# RAM_EMMC_Power.net
KiCad netlist of a schematic drawn in Altium Designer
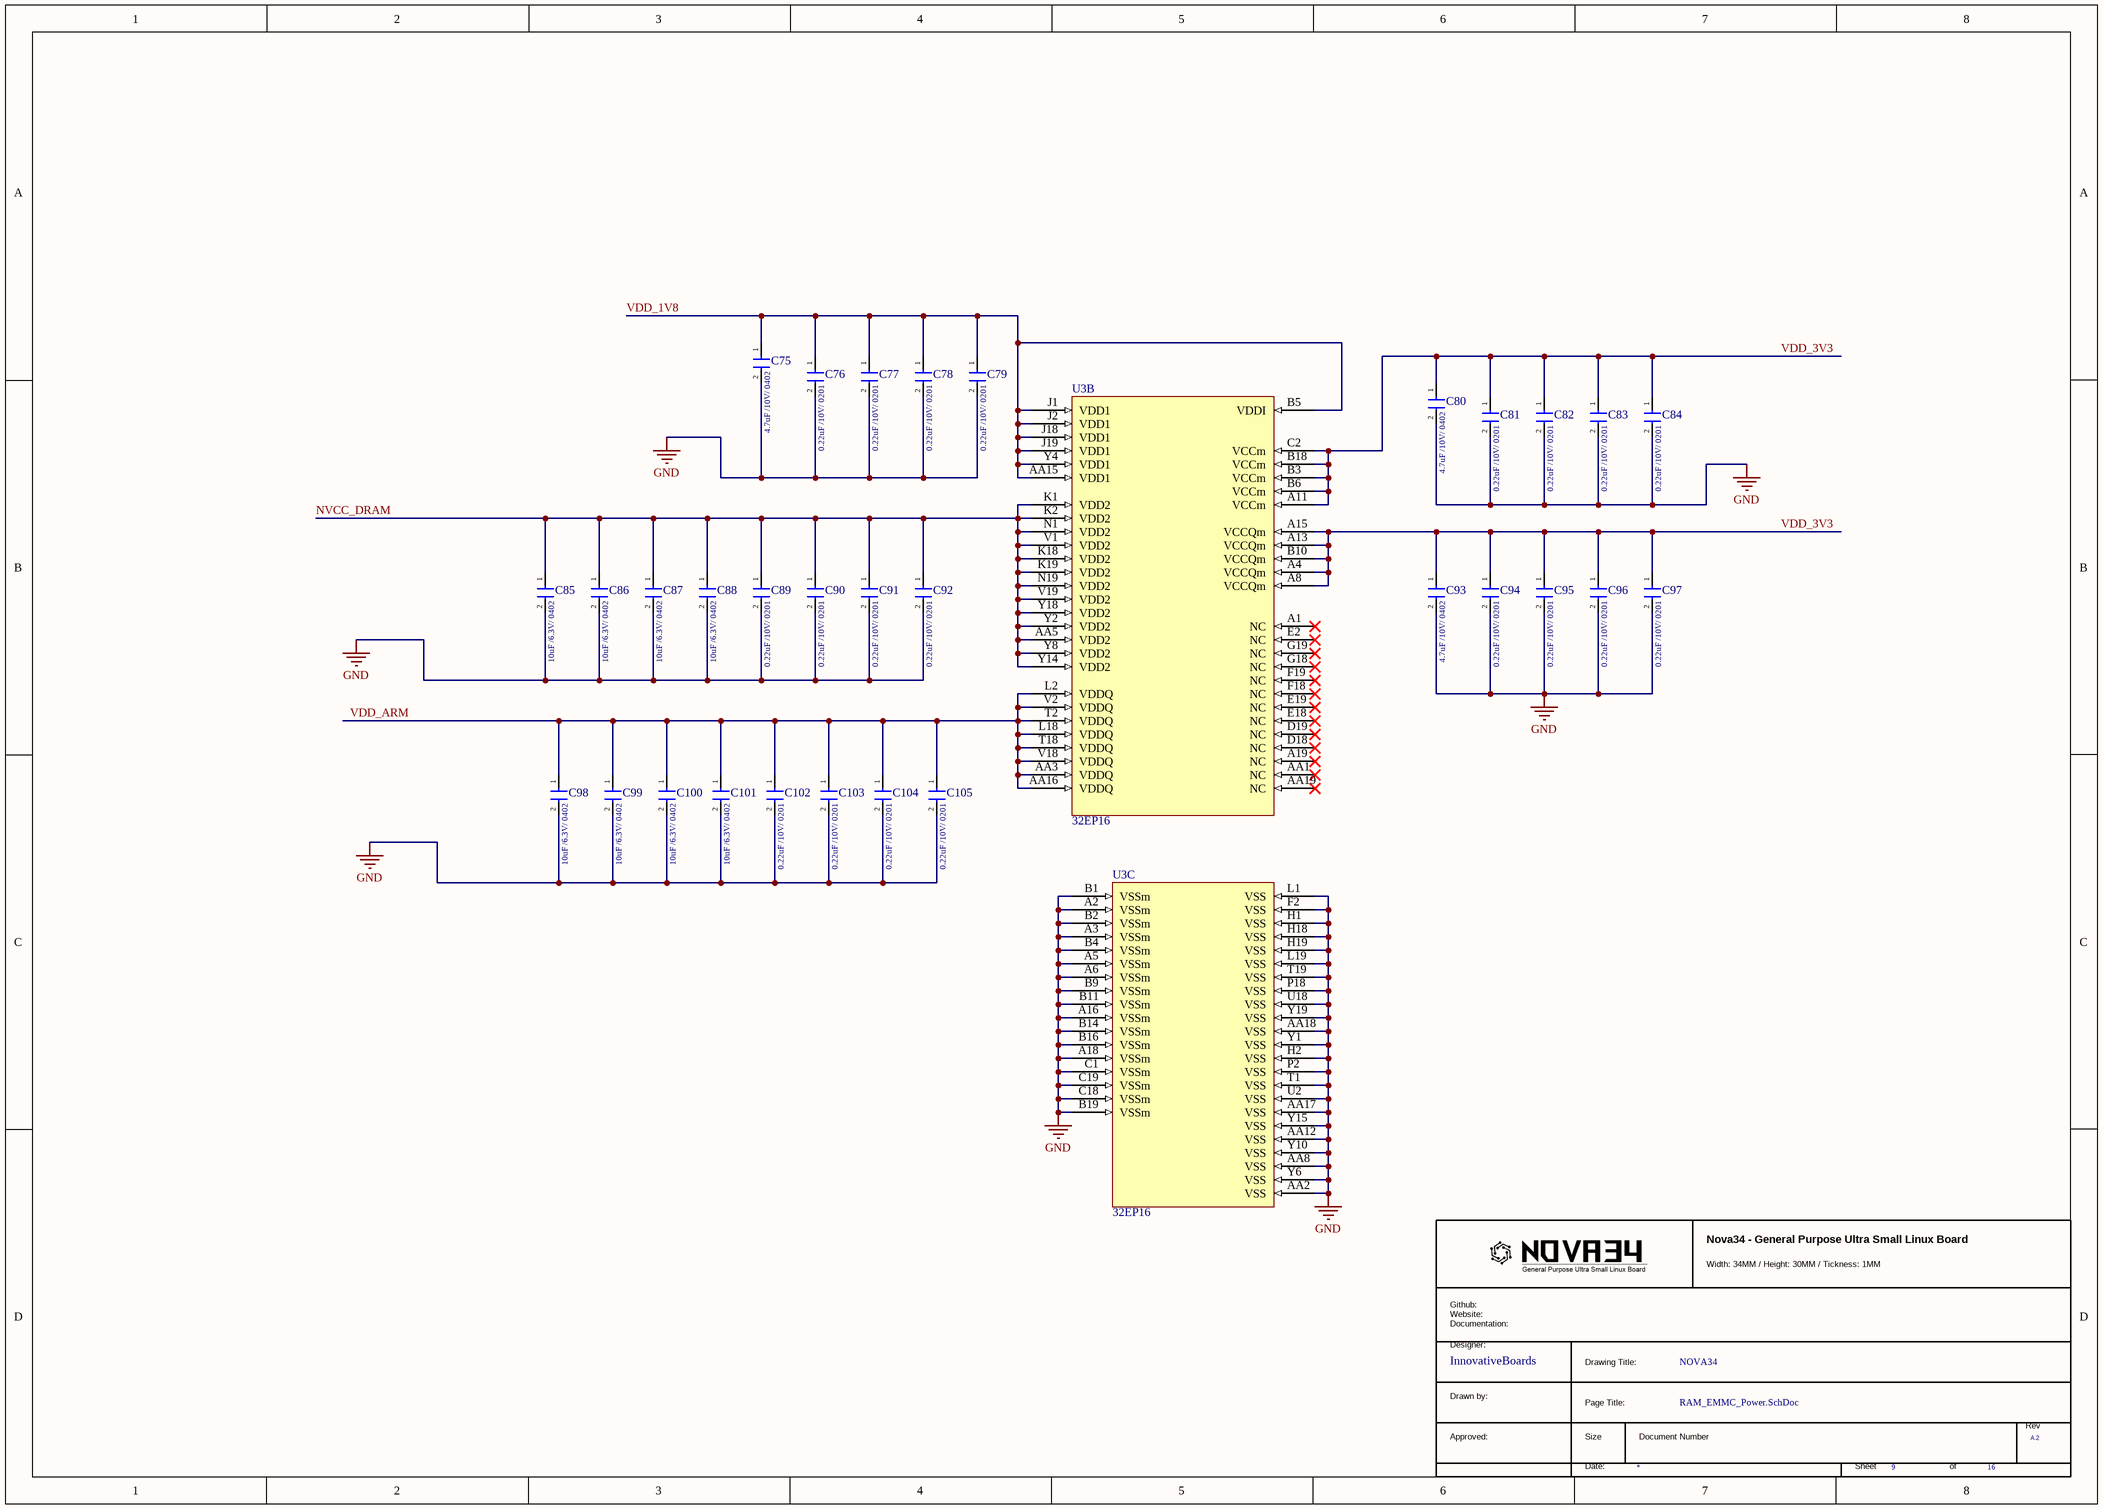
[diagram p0: RAM_EMMC_Power.SchDoc]

(export (version "E")
  (design (tool "Eeschema 10.0.6"))
  (components
    (comp (ref "*")
      (value "TitleBlock_MCPG")
      (fields (field (name "REVCODE") "A.2"))
      (libsource (lib "Nova_SCHLIB") (part "TitleBlock_MCPG"))
    )
    (comp (ref "C75")
      (value "4.7uF /10V/ 0402")
      (footprint "CAPC1005X70N")
      (description "Multilayer Ceramic Capacitors MLCC - SMD/SMT 0402 X6S 4.7 F 20 10VDC AEC-Q200")
      (fields
        (field (name "MANUFACTURER_PART_NUMBER") "GRT155C81A475ME13J")
        (field (name "MOUSER PART NUMBER") "81-GRT155C81A475ME3J")
      )
      (libsource (lib "Nova_SCHLIB") (part "GRT155C81A475ME13J"))
    )
    (comp (ref "C76")
      (value "0.22uF /10V/ 0201")
      (footprint "GRM033D70J224ME01D")
      (description "Multilayer Ceramic Capacitors MLCC - SMD/SMT 0201 10VDC 0.22 F 10 X6S")
      (fields
        (field (name "MANUFACTURER_PART_NUMBER") "GRM033C81A224KE01J")
        (field (name "MOUSER PART NUMBER") "81-GRM033C81A224KE1J")
      )
      (libsource (lib "Nova_SCHLIB") (part "GRM033C81A224KE01J"))
    )
    (comp (ref "C77")
      (value "0.22uF /10V/ 0201")
      (footprint "GRM033D70J224ME01D")
      (description "Multilayer Ceramic Capacitors MLCC - SMD/SMT 0201 10VDC 0.22 F 10 X6S")
      (fields
        (field (name "MANUFACTURER_PART_NUMBER") "GRM033C81A224KE01J")
        (field (name "MOUSER PART NUMBER") "81-GRM033C81A224KE1J")
      )
      (libsource (lib "Nova_SCHLIB") (part "GRM033C81A224KE01J"))
    )
    (comp (ref "C78")
      (value "0.22uF /10V/ 0201")
      (footprint "GRM033D70J224ME01D")
      (description "Multilayer Ceramic Capacitors MLCC - SMD/SMT 0201 10VDC 0.22 F 10 X6S")
      (fields
        (field (name "MANUFACTURER_PART_NUMBER") "GRM033C81A224KE01J")
        (field (name "MOUSER PART NUMBER") "81-GRM033C81A224KE1J")
      )
      (libsource (lib "Nova_SCHLIB") (part "GRM033C81A224KE01J"))
    )
    (comp (ref "C79")
      (value "0.22uF /10V/ 0201")
      (footprint "GRM033D70J224ME01D")
      (description "Multilayer Ceramic Capacitors MLCC - SMD/SMT 0201 10VDC 0.22 F 10 X6S")
      (fields
        (field (name "MANUFACTURER_PART_NUMBER") "GRM033C81A224KE01J")
        (field (name "MOUSER PART NUMBER") "81-GRM033C81A224KE1J")
      )
      (libsource (lib "Nova_SCHLIB") (part "GRM033C81A224KE01J"))
    )
    (comp (ref "C80")
      (value "4.7uF /10V/ 0402")
      (footprint "CAPC1005X70N")
      (description "Multilayer Ceramic Capacitors MLCC - SMD/SMT 0402 X6S 4.7 F 20 10VDC AEC-Q200")
      (fields
        (field (name "MANUFACTURER_PART_NUMBER") "GRT155C81A475ME13J")
        (field (name "MOUSER PART NUMBER") "81-GRT155C81A475ME3J")
      )
      (libsource (lib "Nova_SCHLIB") (part "GRT155C81A475ME13J"))
    )
    (comp (ref "C81")
      (value "0.22uF /10V/ 0201")
      (footprint "GRM033D70J224ME01D")
      (description "Multilayer Ceramic Capacitors MLCC - SMD/SMT 0201 10VDC 0.22 F 10 X6S")
      (fields
        (field (name "MANUFACTURER_PART_NUMBER") "GRM033C81A224KE01J")
        (field (name "MOUSER PART NUMBER") "81-GRM033C81A224KE1J")
      )
      (libsource (lib "Nova_SCHLIB") (part "GRM033C81A224KE01J"))
    )
    (comp (ref "C82")
      (value "0.22uF /10V/ 0201")
      (footprint "GRM033D70J224ME01D")
      (description "Multilayer Ceramic Capacitors MLCC - SMD/SMT 0201 10VDC 0.22 F 10 X6S")
      (fields
        (field (name "MANUFACTURER_PART_NUMBER") "GRM033C81A224KE01J")
        (field (name "MOUSER PART NUMBER") "81-GRM033C81A224KE1J")
      )
      (libsource (lib "Nova_SCHLIB") (part "GRM033C81A224KE01J"))
    )
    (comp (ref "C83")
      (value "0.22uF /10V/ 0201")
      (footprint "GRM033D70J224ME01D")
      (description "Multilayer Ceramic Capacitors MLCC - SMD/SMT 0201 10VDC 0.22 F 10 X6S")
      (fields
        (field (name "MANUFACTURER_PART_NUMBER") "GRM033C81A224KE01J")
        (field (name "MOUSER PART NUMBER") "81-GRM033C81A224KE1J")
      )
      (libsource (lib "Nova_SCHLIB") (part "GRM033C81A224KE01J"))
    )
    (comp (ref "C84")
      (value "0.22uF /10V/ 0201")
      (footprint "GRM033D70J224ME01D")
      (description "Multilayer Ceramic Capacitors MLCC - SMD/SMT 0201 10VDC 0.22 F 10 X6S")
      (fields
        (field (name "MANUFACTURER_PART_NUMBER") "GRM033C81A224KE01J")
        (field (name "MOUSER PART NUMBER") "81-GRM033C81A224KE1J")
      )
      (libsource (lib "Nova_SCHLIB") (part "GRM033C81A224KE01J"))
    )
    (comp (ref "C85")
      (value "10uF /6.3V/ 0402")
      (footprint "CAPC1005X65N")
      (description "Multilayer Ceramic Capacitors MLCC - SMD/SMT 10 uF 6.3 VDC 20% 0402 X5R")
      (fields
        (field (name "MANUFACTURER_PART_NUMBER") "GRM155R60J106ME15D")
        (field (name "MOUSER PART NUMBER") "81-GRM155R60J106ME5D")
      )
      (libsource (lib "Nova_SCHLIB") (part "GRM155R60J106ME15D"))
    )
    (comp (ref "C86")
      (value "10uF /6.3V/ 0402")
      (footprint "CAPC1005X65N")
      (description "Multilayer Ceramic Capacitors MLCC - SMD/SMT 10 uF 6.3 VDC 20% 0402 X5R")
      (fields
        (field (name "MANUFACTURER_PART_NUMBER") "GRM155R60J106ME15D")
        (field (name "MOUSER PART NUMBER") "81-GRM155R60J106ME5D")
      )
      (libsource (lib "Nova_SCHLIB") (part "GRM155R60J106ME15D"))
    )
    (comp (ref "C87")
      (value "10uF /6.3V/ 0402")
      (footprint "CAPC1005X65N")
      (description "Multilayer Ceramic Capacitors MLCC - SMD/SMT 10 uF 6.3 VDC 20% 0402 X5R")
      (fields
        (field (name "MANUFACTURER_PART_NUMBER") "GRM155R60J106ME15D")
        (field (name "MOUSER PART NUMBER") "81-GRM155R60J106ME5D")
      )
      (libsource (lib "Nova_SCHLIB") (part "GRM155R60J106ME15D"))
    )
    (comp (ref "C88")
      (value "10uF /6.3V/ 0402")
      (footprint "CAPC1005X65N")
      (description "Multilayer Ceramic Capacitors MLCC - SMD/SMT 10 uF 6.3 VDC 20% 0402 X5R")
      (fields
        (field (name "MANUFACTURER_PART_NUMBER") "GRM155R60J106ME15D")
        (field (name "MOUSER PART NUMBER") "81-GRM155R60J106ME5D")
      )
      (libsource (lib "Nova_SCHLIB") (part "GRM155R60J106ME15D"))
    )
    (comp (ref "C89")
      (value "0.22uF /10V/ 0201")
      (footprint "GRM033D70J224ME01D")
      (description "Multilayer Ceramic Capacitors MLCC - SMD/SMT 0201 10VDC 0.22 F 10 X6S")
      (fields
        (field (name "MANUFACTURER_PART_NUMBER") "GRM033C81A224KE01J")
        (field (name "MOUSER PART NUMBER") "81-GRM033C81A224KE1J")
      )
      (libsource (lib "Nova_SCHLIB") (part "GRM033C81A224KE01J"))
    )
    (comp (ref "C90")
      (value "0.22uF /10V/ 0201")
      (footprint "GRM033D70J224ME01D")
      (description "Multilayer Ceramic Capacitors MLCC - SMD/SMT 0201 10VDC 0.22 F 10 X6S")
      (fields
        (field (name "MANUFACTURER_PART_NUMBER") "GRM033C81A224KE01J")
        (field (name "MOUSER PART NUMBER") "81-GRM033C81A224KE1J")
      )
      (libsource (lib "Nova_SCHLIB") (part "GRM033C81A224KE01J"))
    )
    (comp (ref "C91")
      (value "0.22uF /10V/ 0201")
      (footprint "GRM033D70J224ME01D")
      (description "Multilayer Ceramic Capacitors MLCC - SMD/SMT 0201 10VDC 0.22 F 10 X6S")
      (fields
        (field (name "MANUFACTURER_PART_NUMBER") "GRM033C81A224KE01J")
        (field (name "MOUSER PART NUMBER") "81-GRM033C81A224KE1J")
      )
      (libsource (lib "Nova_SCHLIB") (part "GRM033C81A224KE01J"))
    )
    (comp (ref "C92")
      (value "0.22uF /10V/ 0201")
      (footprint "GRM033D70J224ME01D")
      (description "Multilayer Ceramic Capacitors MLCC - SMD/SMT 0201 10VDC 0.22 F 10 X6S")
      (fields
        (field (name "MANUFACTURER_PART_NUMBER") "GRM033C81A224KE01J")
        (field (name "MOUSER PART NUMBER") "81-GRM033C81A224KE1J")
      )
      (libsource (lib "Nova_SCHLIB") (part "GRM033C81A224KE01J"))
    )
    (comp (ref "C93")
      (value "4.7uF /10V/ 0402")
      (footprint "CAPC1005X70N")
      (description "Multilayer Ceramic Capacitors MLCC - SMD/SMT 0402 X6S 4.7 F 20 10VDC AEC-Q200")
      (fields
        (field (name "MANUFACTURER_PART_NUMBER") "GRT155C81A475ME13J")
        (field (name "MOUSER PART NUMBER") "81-GRT155C81A475ME3J")
      )
      (libsource (lib "Nova_SCHLIB") (part "GRT155C81A475ME13J"))
    )
    (comp (ref "C94")
      (value "0.22uF /10V/ 0201")
      (footprint "GRM033D70J224ME01D")
      (description "Multilayer Ceramic Capacitors MLCC - SMD/SMT 0201 10VDC 0.22 F 10 X6S")
      (fields
        (field (name "MANUFACTURER_PART_NUMBER") "GRM033C81A224KE01J")
        (field (name "MOUSER PART NUMBER") "81-GRM033C81A224KE1J")
      )
      (libsource (lib "Nova_SCHLIB") (part "GRM033C81A224KE01J"))
    )
    (comp (ref "C95")
      (value "0.22uF /10V/ 0201")
      (footprint "GRM033D70J224ME01D")
      (description "Multilayer Ceramic Capacitors MLCC - SMD/SMT 0201 10VDC 0.22 F 10 X6S")
      (fields
        (field (name "MANUFACTURER_PART_NUMBER") "GRM033C81A224KE01J")
        (field (name "MOUSER PART NUMBER") "81-GRM033C81A224KE1J")
      )
      (libsource (lib "Nova_SCHLIB") (part "GRM033C81A224KE01J"))
    )
    (comp (ref "C96")
      (value "0.22uF /10V/ 0201")
      (footprint "GRM033D70J224ME01D")
      (description "Multilayer Ceramic Capacitors MLCC - SMD/SMT 0201 10VDC 0.22 F 10 X6S")
      (fields
        (field (name "MANUFACTURER_PART_NUMBER") "GRM033C81A224KE01J")
        (field (name "MOUSER PART NUMBER") "81-GRM033C81A224KE1J")
      )
      (libsource (lib "Nova_SCHLIB") (part "GRM033C81A224KE01J"))
    )
    (comp (ref "C97")
      (value "0.22uF /10V/ 0201")
      (footprint "GRM033D70J224ME01D")
      (description "Multilayer Ceramic Capacitors MLCC - SMD/SMT 0201 10VDC 0.22 F 10 X6S")
      (fields
        (field (name "MANUFACTURER_PART_NUMBER") "GRM033C81A224KE01J")
        (field (name "MOUSER PART NUMBER") "81-GRM033C81A224KE1J")
      )
      (libsource (lib "Nova_SCHLIB") (part "GRM033C81A224KE01J"))
    )
    (comp (ref "C98")
      (value "10uF /6.3V/ 0402")
      (footprint "CAPC1005X65N")
      (description "Multilayer Ceramic Capacitors MLCC - SMD/SMT 10 uF 6.3 VDC 20% 0402 X5R")
      (fields
        (field (name "MANUFACTURER_PART_NUMBER") "GRM155R60J106ME15D")
        (field (name "MOUSER PART NUMBER") "81-GRM155R60J106ME5D")
      )
      (libsource (lib "Nova_SCHLIB") (part "GRM155R60J106ME15D"))
    )
    (comp (ref "C99")
      (value "10uF /6.3V/ 0402")
      (footprint "CAPC1005X65N")
      (description "Multilayer Ceramic Capacitors MLCC - SMD/SMT 10 uF 6.3 VDC 20% 0402 X5R")
      (fields
        (field (name "MANUFACTURER_PART_NUMBER") "GRM155R60J106ME15D")
        (field (name "MOUSER PART NUMBER") "81-GRM155R60J106ME5D")
      )
      (libsource (lib "Nova_SCHLIB") (part "GRM155R60J106ME15D"))
    )
    (comp (ref "C100")
      (value "10uF /6.3V/ 0402")
      (footprint "CAPC1005X65N")
      (description "Multilayer Ceramic Capacitors MLCC - SMD/SMT 10 uF 6.3 VDC 20% 0402 X5R")
      (fields
        (field (name "MANUFACTURER_PART_NUMBER") "GRM155R60J106ME15D")
        (field (name "MOUSER PART NUMBER") "81-GRM155R60J106ME5D")
      )
      (libsource (lib "Nova_SCHLIB") (part "GRM155R60J106ME15D"))
    )
    (comp (ref "C101")
      (value "10uF /6.3V/ 0402")
      (footprint "CAPC1005X65N")
      (description "Multilayer Ceramic Capacitors MLCC - SMD/SMT 10 uF 6.3 VDC 20% 0402 X5R")
      (fields
        (field (name "MANUFACTURER_PART_NUMBER") "GRM155R60J106ME15D")
        (field (name "MOUSER PART NUMBER") "81-GRM155R60J106ME5D")
      )
      (libsource (lib "Nova_SCHLIB") (part "GRM155R60J106ME15D"))
    )
    (comp (ref "C102")
      (value "0.22uF /10V/ 0201")
      (footprint "GRM033D70J224ME01D")
      (description "Multilayer Ceramic Capacitors MLCC - SMD/SMT 0201 10VDC 0.22 F 10 X6S")
      (fields
        (field (name "MANUFACTURER_PART_NUMBER") "GRM033C81A224KE01J")
        (field (name "MOUSER PART NUMBER") "81-GRM033C81A224KE1J")
      )
      (libsource (lib "Nova_SCHLIB") (part "GRM033C81A224KE01J"))
    )
    (comp (ref "C103")
      (value "0.22uF /10V/ 0201")
      (footprint "GRM033D70J224ME01D")
      (description "Multilayer Ceramic Capacitors MLCC - SMD/SMT 0201 10VDC 0.22 F 10 X6S")
      (fields
        (field (name "MANUFACTURER_PART_NUMBER") "GRM033C81A224KE01J")
        (field (name "MOUSER PART NUMBER") "81-GRM033C81A224KE1J")
      )
      (libsource (lib "Nova_SCHLIB") (part "GRM033C81A224KE01J"))
    )
    (comp (ref "C104")
      (value "0.22uF /10V/ 0201")
      (footprint "GRM033D70J224ME01D")
      (description "Multilayer Ceramic Capacitors MLCC - SMD/SMT 0201 10VDC 0.22 F 10 X6S")
      (fields
        (field (name "MANUFACTURER_PART_NUMBER") "GRM033C81A224KE01J")
        (field (name "MOUSER PART NUMBER") "81-GRM033C81A224KE1J")
      )
      (libsource (lib "Nova_SCHLIB") (part "GRM033C81A224KE01J"))
    )
    (comp (ref "C105")
      (value "0.22uF /10V/ 0201")
      (footprint "GRM033D70J224ME01D")
      (description "Multilayer Ceramic Capacitors MLCC - SMD/SMT 0201 10VDC 0.22 F 10 X6S")
      (fields
        (field (name "MANUFACTURER_PART_NUMBER") "GRM033C81A224KE01J")
        (field (name "MOUSER PART NUMBER") "81-GRM033C81A224KE1J")
      )
      (libsource (lib "Nova_SCHLIB") (part "GRM033C81A224KE01J"))
    )
    (comp (ref "U3")
      (value "32EP16")
      (footprint "BGA144C40P19X21_800X950X80")
      (libsource (lib "Nova_SCHLIB") (part "32EP16"))
    )
  )
  (nets
    (net (code "1") (name "/NVCC_DRAM") (class "Default")
      (node (ref "C85") (pin "1") (pinfunction "1_1") (pintype "passive"))
      (node (ref "C86") (pin "1") (pinfunction "1_1") (pintype "passive"))
      (node (ref "C87") (pin "1") (pinfunction "1_1") (pintype "passive"))
      (node (ref "C88") (pin "1") (pinfunction "1_1") (pintype "passive"))
      (node (ref "C89") (pin "1") (pinfunction "1_1") (pintype "passive"))
      (node (ref "C90") (pin "1") (pinfunction "1_1") (pintype "passive"))
      (node (ref "C91") (pin "1") (pinfunction "1_1") (pintype "passive"))
      (node (ref "C92") (pin "1") (pinfunction "1_1") (pintype "passive"))
      (node (ref "U3") (pin "AA5") (pinfunction "VDD2_AA5") (pintype "input"))
      (node (ref "U3") (pin "K1") (pinfunction "VDD2_K1") (pintype "input"))
      (node (ref "U3") (pin "K18") (pinfunction "VDD2_K18") (pintype "input"))
      (node (ref "U3") (pin "K19") (pinfunction "VDD2_K19") (pintype "input"))
      (node (ref "U3") (pin "K2") (pinfunction "VDD2_K2") (pintype "input"))
      (node (ref "U3") (pin "N1") (pinfunction "VDD2_N1") (pintype "input"))
      (node (ref "U3") (pin "N19") (pinfunction "VDD2_N19") (pintype "input"))
      (node (ref "U3") (pin "V1") (pinfunction "VDD2_V1") (pintype "input"))
      (node (ref "U3") (pin "V19") (pinfunction "VDD2_V19") (pintype "input"))
      (node (ref "U3") (pin "Y14") (pinfunction "VDD2_Y14") (pintype "input"))
      (node (ref "U3") (pin "Y18") (pinfunction "VDD2_Y18") (pintype "input"))
      (node (ref "U3") (pin "Y2") (pinfunction "VDD2_Y2") (pintype "input"))
      (node (ref "U3") (pin "Y8") (pinfunction "VDD2_Y8") (pintype "input"))
    )
    (net (code "2") (name "/VDD_1V8") (class "Default")
      (node (ref "C75") (pin "1") (pinfunction "1_1") (pintype "passive"))
      (node (ref "C76") (pin "1") (pinfunction "1_1") (pintype "passive"))
      (node (ref "C77") (pin "1") (pinfunction "1_1") (pintype "passive"))
      (node (ref "C78") (pin "1") (pinfunction "1_1") (pintype "passive"))
      (node (ref "C79") (pin "1") (pinfunction "1_1") (pintype "passive"))
      (node (ref "U3") (pin "AA15") (pinfunction "VDD1_AA15") (pintype "input"))
      (node (ref "U3") (pin "B5") (pinfunction "VDDI_B5") (pintype "input"))
      (node (ref "U3") (pin "J1") (pinfunction "VDD1_J1") (pintype "input"))
      (node (ref "U3") (pin "J18") (pinfunction "VDD1_J18") (pintype "input"))
      (node (ref "U3") (pin "J19") (pinfunction "VDD1_J19") (pintype "input"))
      (node (ref "U3") (pin "J2") (pinfunction "VDD1_J2") (pintype "input"))
      (node (ref "U3") (pin "Y4") (pinfunction "VDD1_Y4") (pintype "input"))
    )
    (net (code "3") (name "/VDD_3V3") (class "Default")
      (node (ref "C80") (pin "1") (pinfunction "1_1") (pintype "passive"))
      (node (ref "C81") (pin "1") (pinfunction "1_1") (pintype "passive"))
      (node (ref "C82") (pin "1") (pinfunction "1_1") (pintype "passive"))
      (node (ref "C83") (pin "1") (pinfunction "1_1") (pintype "passive"))
      (node (ref "C84") (pin "1") (pinfunction "1_1") (pintype "passive"))
      (node (ref "C93") (pin "1") (pinfunction "1_1") (pintype "passive"))
      (node (ref "C94") (pin "1") (pinfunction "1_1") (pintype "passive"))
      (node (ref "C95") (pin "1") (pinfunction "1_1") (pintype "passive"))
      (node (ref "C96") (pin "1") (pinfunction "1_1") (pintype "passive"))
      (node (ref "C97") (pin "1") (pinfunction "1_1") (pintype "passive"))
      (node (ref "U3") (pin "A11") (pinfunction "VCCm_A11") (pintype "input"))
      (node (ref "U3") (pin "A13") (pinfunction "VCCQm_A13") (pintype "input"))
      (node (ref "U3") (pin "A15") (pinfunction "VCCQm_A15") (pintype "input"))
      (node (ref "U3") (pin "A4") (pinfunction "VCCQm_A4") (pintype "input"))
      (node (ref "U3") (pin "A8") (pinfunction "VCCQm_A8") (pintype "input"))
      (node (ref "U3") (pin "B10") (pinfunction "VCCQm_B10") (pintype "input"))
      (node (ref "U3") (pin "B18") (pinfunction "VCCm_B18") (pintype "input"))
      (node (ref "U3") (pin "B3") (pinfunction "VCCm_B3") (pintype "input"))
      (node (ref "U3") (pin "B6") (pinfunction "VCCm_B6") (pintype "input"))
      (node (ref "U3") (pin "C2") (pinfunction "VCCm_C2") (pintype "input"))
    )
    (net (code "4") (name "/VDD_ARM") (class "Default")
      (node (ref "C100") (pin "1") (pinfunction "1_1") (pintype "passive"))
      (node (ref "C101") (pin "1") (pinfunction "1_1") (pintype "passive"))
      (node (ref "C102") (pin "1") (pinfunction "1_1") (pintype "passive"))
      (node (ref "C103") (pin "1") (pinfunction "1_1") (pintype "passive"))
      (node (ref "C104") (pin "1") (pinfunction "1_1") (pintype "passive"))
      (node (ref "C105") (pin "1") (pinfunction "1_1") (pintype "passive"))
      (node (ref "C98") (pin "1") (pinfunction "1_1") (pintype "passive"))
      (node (ref "C99") (pin "1") (pinfunction "1_1") (pintype "passive"))
      (node (ref "U3") (pin "AA16") (pinfunction "VDDQ_AA16") (pintype "input"))
      (node (ref "U3") (pin "AA3") (pinfunction "VDDQ_AA3") (pintype "input"))
      (node (ref "U3") (pin "L18") (pinfunction "VDDQ_L18") (pintype "input"))
      (node (ref "U3") (pin "L2") (pinfunction "VDDQ_L2") (pintype "input"))
      (node (ref "U3") (pin "T18") (pinfunction "VDDQ_T18") (pintype "input"))
      (node (ref "U3") (pin "T2") (pinfunction "VDDQ_T2") (pintype "input"))
      (node (ref "U3") (pin "V18") (pinfunction "VDDQ_V18") (pintype "input"))
      (node (ref "U3") (pin "V2") (pinfunction "VDDQ_V2") (pintype "input"))
    )
    (net (code "5") (name "GND") (class "Default")
      (node (ref "C100") (pin "2") (pinfunction "2_2") (pintype "passive"))
      (node (ref "C101") (pin "2") (pinfunction "2_2") (pintype "passive"))
      (node (ref "C102") (pin "2") (pinfunction "2_2") (pintype "passive"))
      (node (ref "C103") (pin "2") (pinfunction "2_2") (pintype "passive"))
      (node (ref "C104") (pin "2") (pinfunction "2_2") (pintype "passive"))
      (node (ref "C105") (pin "2") (pinfunction "2_2") (pintype "passive"))
      (node (ref "C75") (pin "2") (pinfunction "2_2") (pintype "passive"))
      (node (ref "C76") (pin "2") (pinfunction "2_2") (pintype "passive"))
      (node (ref "C77") (pin "2") (pinfunction "2_2") (pintype "passive"))
      (node (ref "C78") (pin "2") (pinfunction "2_2") (pintype "passive"))
      (node (ref "C79") (pin "2") (pinfunction "2_2") (pintype "passive"))
      (node (ref "C80") (pin "2") (pinfunction "2_2") (pintype "passive"))
      (node (ref "C81") (pin "2") (pinfunction "2_2") (pintype "passive"))
      (node (ref "C82") (pin "2") (pinfunction "2_2") (pintype "passive"))
      (node (ref "C83") (pin "2") (pinfunction "2_2") (pintype "passive"))
      (node (ref "C84") (pin "2") (pinfunction "2_2") (pintype "passive"))
      (node (ref "C85") (pin "2") (pinfunction "2_2") (pintype "passive"))
      (node (ref "C86") (pin "2") (pinfunction "2_2") (pintype "passive"))
      (node (ref "C87") (pin "2") (pinfunction "2_2") (pintype "passive"))
      (node (ref "C88") (pin "2") (pinfunction "2_2") (pintype "passive"))
      (node (ref "C89") (pin "2") (pinfunction "2_2") (pintype "passive"))
      (node (ref "C90") (pin "2") (pinfunction "2_2") (pintype "passive"))
      (node (ref "C91") (pin "2") (pinfunction "2_2") (pintype "passive"))
      (node (ref "C92") (pin "2") (pinfunction "2_2") (pintype "passive"))
      (node (ref "C93") (pin "2") (pinfunction "2_2") (pintype "passive"))
      (node (ref "C94") (pin "2") (pinfunction "2_2") (pintype "passive"))
      (node (ref "C95") (pin "2") (pinfunction "2_2") (pintype "passive"))
      (node (ref "C96") (pin "2") (pinfunction "2_2") (pintype "passive"))
      (node (ref "C97") (pin "2") (pinfunction "2_2") (pintype "passive"))
      (node (ref "C98") (pin "2") (pinfunction "2_2") (pintype "passive"))
      (node (ref "C99") (pin "2") (pinfunction "2_2") (pintype "passive"))
      (node (ref "U3") (pin "A16") (pinfunction "VSSm_A16") (pintype "input"))
      (node (ref "U3") (pin "A18") (pinfunction "VSSm_A18") (pintype "input"))
      (node (ref "U3") (pin "A2") (pinfunction "VSSm_A2") (pintype "input"))
      (node (ref "U3") (pin "A3") (pinfunction "VSSm_A3") (pintype "input"))
      (node (ref "U3") (pin "A5") (pinfunction "VSSm_A5") (pintype "input"))
      (node (ref "U3") (pin "A6") (pinfunction "VSSm_A6") (pintype "input"))
      (node (ref "U3") (pin "AA12") (pinfunction "VSS_AA12") (pintype "input"))
      (node (ref "U3") (pin "AA17") (pinfunction "VSS_AA17") (pintype "input"))
      (node (ref "U3") (pin "AA18") (pinfunction "VSS_AA18") (pintype "input"))
      (node (ref "U3") (pin "AA2") (pinfunction "VSS_AA2") (pintype "input"))
      (node (ref "U3") (pin "AA8") (pinfunction "VSS_AA8") (pintype "input"))
      (node (ref "U3") (pin "B1") (pinfunction "VSSm_B1") (pintype "input"))
      (node (ref "U3") (pin "B11") (pinfunction "VSSm_B11") (pintype "input"))
      (node (ref "U3") (pin "B14") (pinfunction "VSSm_B14") (pintype "input"))
      (node (ref "U3") (pin "B16") (pinfunction "VSSm_B16") (pintype "input"))
      (node (ref "U3") (pin "B19") (pinfunction "VSSm_B19") (pintype "input"))
      (node (ref "U3") (pin "B2") (pinfunction "VSSm_B2") (pintype "input"))
      (node (ref "U3") (pin "B4") (pinfunction "VSSm_B4") (pintype "input"))
      (node (ref "U3") (pin "B9") (pinfunction "VSSm_B9") (pintype "input"))
      (node (ref "U3") (pin "C1") (pinfunction "VSSm_C1") (pintype "input"))
      (node (ref "U3") (pin "C18") (pinfunction "VSSm_C18") (pintype "input"))
      (node (ref "U3") (pin "C19") (pinfunction "VSSm_C19") (pintype "input"))
      (node (ref "U3") (pin "F2") (pinfunction "VSS_F2") (pintype "input"))
      (node (ref "U3") (pin "H1") (pinfunction "VSS_H1") (pintype "input"))
      (node (ref "U3") (pin "H18") (pinfunction "VSS_H18") (pintype "input"))
      (node (ref "U3") (pin "H19") (pinfunction "VSS_H19") (pintype "input"))
      (node (ref "U3") (pin "H2") (pinfunction "VSS_H2") (pintype "input"))
      (node (ref "U3") (pin "L1") (pinfunction "VSS_L1") (pintype "input"))
      (node (ref "U3") (pin "L19") (pinfunction "VSS_L19") (pintype "input"))
      (node (ref "U3") (pin "P18") (pinfunction "VSS_P18") (pintype "input"))
      (node (ref "U3") (pin "P2") (pinfunction "VSS_P2") (pintype "input"))
      (node (ref "U3") (pin "T1") (pinfunction "VSS_T1") (pintype "input"))
      (node (ref "U3") (pin "T19") (pinfunction "VSS_T19") (pintype "input"))
      (node (ref "U3") (pin "U18") (pinfunction "VSS_U18") (pintype "input"))
      (node (ref "U3") (pin "U2") (pinfunction "VSS_U2") (pintype "input"))
      (node (ref "U3") (pin "Y1") (pinfunction "VSS_Y1") (pintype "input"))
      (node (ref "U3") (pin "Y10") (pinfunction "VSS_Y10") (pintype "input"))
      (node (ref "U3") (pin "Y15") (pinfunction "VSS_Y15") (pintype "input"))
      (node (ref "U3") (pin "Y19") (pinfunction "VSS_Y19") (pintype "input"))
      (node (ref "U3") (pin "Y6") (pinfunction "VSS_Y6") (pintype "input"))
    )
    (net (code "6") (name "unconnected-(U3B-NC-PadA1)") (class "Default")
      (node (ref "U3") (pin "A1") (pinfunction "NC_A1") (pintype "input+no_connect"))
    )
    (net (code "7") (name "unconnected-(U3B-NC-PadA19)") (class "Default")
      (node (ref "U3") (pin "A19") (pinfunction "NC_A19") (pintype "input+no_connect"))
    )
    (net (code "8") (name "unconnected-(U3B-NC-PadAA1)") (class "Default")
      (node (ref "U3") (pin "AA1") (pinfunction "NC_AA1") (pintype "input+no_connect"))
    )
    (net (code "9") (name "unconnected-(U3B-NC-PadAA19)") (class "Default")
      (node (ref "U3") (pin "AA19") (pinfunction "NC_AA19") (pintype "input+no_connect"))
    )
    (net (code "10") (name "unconnected-(U3B-NC-PadD18)") (class "Default")
      (node (ref "U3") (pin "D18") (pinfunction "NC_D18") (pintype "input+no_connect"))
    )
    (net (code "11") (name "unconnected-(U3B-NC-PadD19)") (class "Default")
      (node (ref "U3") (pin "D19") (pinfunction "NC_D19") (pintype "input+no_connect"))
    )
    (net (code "12") (name "unconnected-(U3B-NC-PadE2)") (class "Default")
      (node (ref "U3") (pin "E2") (pinfunction "NC_E2") (pintype "input+no_connect"))
    )
    (net (code "13") (name "unconnected-(U3B-NC-PadE18)") (class "Default")
      (node (ref "U3") (pin "E18") (pinfunction "NC_E18") (pintype "input+no_connect"))
    )
    (net (code "14") (name "unconnected-(U3B-NC-PadE19)") (class "Default")
      (node (ref "U3") (pin "E19") (pinfunction "NC_E19") (pintype "input+no_connect"))
    )
    (net (code "15") (name "unconnected-(U3B-NC-PadF18)") (class "Default")
      (node (ref "U3") (pin "F18") (pinfunction "NC_F18") (pintype "input+no_connect"))
    )
    (net (code "16") (name "unconnected-(U3B-NC-PadF19)") (class "Default")
      (node (ref "U3") (pin "F19") (pinfunction "NC_F19") (pintype "input+no_connect"))
    )
    (net (code "17") (name "unconnected-(U3B-NC-PadG18)") (class "Default")
      (node (ref "U3") (pin "G18") (pinfunction "NC_G18") (pintype "input+no_connect"))
    )
    (net (code "18") (name "unconnected-(U3B-NC-PadG19)") (class "Default")
      (node (ref "U3") (pin "G19") (pinfunction "NC_G19") (pintype "input+no_connect"))
    )
  )
)
